# driver.net
KiCad netlist of a schematic drawn in EAGLE
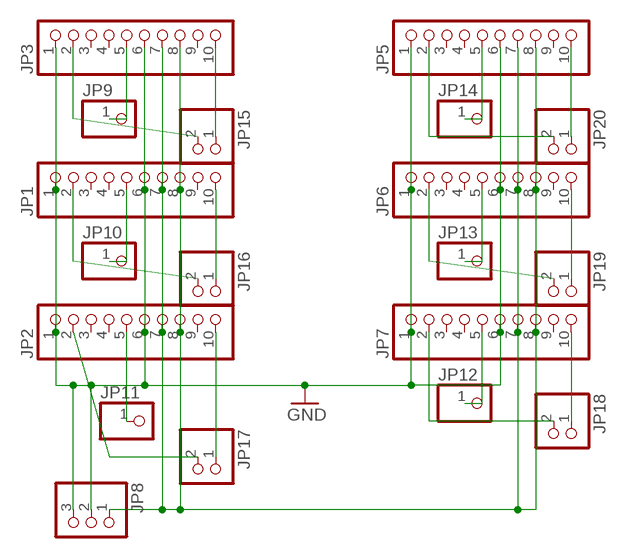
[diagram p0: schematic, sheet 1]

(export (version "E")
  (design (tool "Eeschema 10.0.6"))
  (components
    (comp (ref "JP1")
      (value "PINHD-1X10")
      (footprint "eagle-import:1X10")
      (libsource (lib "eagle-import") (part "PINHD-1X10"))
    )
    (comp (ref "JP2")
      (value "PINHD-1X10")
      (footprint "eagle-import:1X10")
      (libsource (lib "eagle-import") (part "PINHD-1X10"))
    )
    (comp (ref "JP3")
      (value "PINHD-1X10")
      (footprint "eagle-import:1X10")
      (libsource (lib "eagle-import") (part "PINHD-1X10"))
    )
    (comp (ref "JP5")
      (value "PINHD-1X10")
      (footprint "eagle-import:1X10")
      (libsource (lib "eagle-import") (part "PINHD-1X10"))
    )
    (comp (ref "JP6")
      (value "PINHD-1X10")
      (footprint "eagle-import:1X10")
      (libsource (lib "eagle-import") (part "PINHD-1X10"))
    )
    (comp (ref "JP7")
      (value "PINHD-1X10")
      (footprint "eagle-import:1X10")
      (libsource (lib "eagle-import") (part "PINHD-1X10"))
    )
    (comp (ref "JP8")
      (value "PINHD-1X3")
      (footprint "eagle-import:1X03")
      (libsource (lib "eagle-import") (part "PINHD-1X3"))
    )
    (comp (ref "JP9")
      (value "PINHD-1X1")
      (footprint "eagle-import:1X01")
      (libsource (lib "eagle-import") (part "PINHD-1X1"))
    )
    (comp (ref "JP10")
      (value "PINHD-1X1")
      (footprint "eagle-import:1X01")
      (libsource (lib "eagle-import") (part "PINHD-1X1"))
    )
    (comp (ref "JP11")
      (value "PINHD-1X1")
      (footprint "eagle-import:1X01")
      (libsource (lib "eagle-import") (part "PINHD-1X1"))
    )
    (comp (ref "JP12")
      (value "PINHD-1X1")
      (footprint "eagle-import:1X01")
      (libsource (lib "eagle-import") (part "PINHD-1X1"))
    )
    (comp (ref "JP13")
      (value "PINHD-1X1")
      (footprint "eagle-import:1X01")
      (libsource (lib "eagle-import") (part "PINHD-1X1"))
    )
    (comp (ref "JP14")
      (value "PINHD-1X1")
      (footprint "eagle-import:1X01")
      (libsource (lib "eagle-import") (part "PINHD-1X1"))
    )
    (comp (ref "JP15")
      (value "PINHD-1X2")
      (footprint "eagle-import:1X02")
      (libsource (lib "eagle-import") (part "PINHD-1X2"))
    )
    (comp (ref "JP16")
      (value "PINHD-1X2")
      (footprint "eagle-import:1X02")
      (libsource (lib "eagle-import") (part "PINHD-1X2"))
    )
    (comp (ref "JP17")
      (value "PINHD-1X2")
      (footprint "eagle-import:1X02")
      (libsource (lib "eagle-import") (part "PINHD-1X2"))
    )
    (comp (ref "JP18")
      (value "PINHD-1X2")
      (footprint "eagle-import:1X02")
      (libsource (lib "eagle-import") (part "PINHD-1X2"))
    )
    (comp (ref "JP19")
      (value "PINHD-1X2")
      (footprint "eagle-import:1X02")
      (libsource (lib "eagle-import") (part "PINHD-1X2"))
    )
    (comp (ref "JP20")
      (value "PINHD-1X2")
      (footprint "eagle-import:1X02")
      (libsource (lib "eagle-import") (part "PINHD-1X2"))
    )
  )
  (nets
    (net (code "1") (name "GND") (class "Default")
      (node (ref "JP1") (pin "1") (pinfunction "1_1") (pintype "passive"))
      (node (ref "JP1") (pin "6") (pinfunction "6_6") (pintype "passive"))
      (node (ref "JP2") (pin "1") (pinfunction "1_1") (pintype "passive"))
      (node (ref "JP2") (pin "6") (pinfunction "6_6") (pintype "passive"))
      (node (ref "JP3") (pin "1") (pinfunction "1_1") (pintype "passive"))
      (node (ref "JP3") (pin "6") (pinfunction "6_6") (pintype "passive"))
      (node (ref "JP5") (pin "1") (pinfunction "1_1") (pintype "passive"))
      (node (ref "JP5") (pin "6") (pinfunction "6_6") (pintype "passive"))
      (node (ref "JP6") (pin "1") (pinfunction "1_1") (pintype "passive"))
      (node (ref "JP6") (pin "6") (pinfunction "6_6") (pintype "passive"))
      (node (ref "JP7") (pin "1") (pinfunction "1_1") (pintype "passive"))
      (node (ref "JP7") (pin "6") (pinfunction "6_6") (pintype "passive"))
      (node (ref "JP8") (pin "2") (pinfunction "2_2") (pintype "passive"))
      (node (ref "JP8") (pin "3") (pinfunction "3_3") (pintype "passive"))
    )
    (net (code "2") (name "Net-(JP1-Pad2)") (class "Default")
      (node (ref "JP1") (pin "2") (pinfunction "2_2") (pintype "passive"))
      (node (ref "JP16") (pin "2") (pinfunction "2_2") (pintype "passive"))
    )
    (net (code "3") (name "Net-(JP1-Pad5)") (class "Default")
      (node (ref "JP1") (pin "5") (pinfunction "5_5") (pintype "passive"))
      (node (ref "JP10") (pin "1") (pinfunction "1_1") (pintype "passive"))
    )
    (net (code "4") (name "Net-(JP1-Pad7)") (class "Default")
      (node (ref "JP1") (pin "7") (pinfunction "7_7") (pintype "passive"))
      (node (ref "JP1") (pin "8") (pinfunction "8_8") (pintype "passive"))
      (node (ref "JP2") (pin "7") (pinfunction "7_7") (pintype "passive"))
      (node (ref "JP2") (pin "8") (pinfunction "8_8") (pintype "passive"))
      (node (ref "JP3") (pin "7") (pinfunction "7_7") (pintype "passive"))
      (node (ref "JP3") (pin "8") (pinfunction "8_8") (pintype "passive"))
      (node (ref "JP5") (pin "7") (pinfunction "7_7") (pintype "passive"))
      (node (ref "JP5") (pin "8") (pinfunction "8_8") (pintype "passive"))
      (node (ref "JP6") (pin "7") (pinfunction "7_7") (pintype "passive"))
      (node (ref "JP6") (pin "8") (pinfunction "8_8") (pintype "passive"))
      (node (ref "JP7") (pin "7") (pinfunction "7_7") (pintype "passive"))
      (node (ref "JP7") (pin "8") (pinfunction "8_8") (pintype "passive"))
      (node (ref "JP8") (pin "1") (pinfunction "1_1") (pintype "passive"))
    )
    (net (code "5") (name "Net-(JP1-Pad10)") (class "Default")
      (node (ref "JP1") (pin "10") (pinfunction "10_10") (pintype "passive"))
      (node (ref "JP16") (pin "1") (pinfunction "1_1") (pintype "passive"))
    )
    (net (code "6") (name "Net-(JP3-Pad5)") (class "Default")
      (node (ref "JP3") (pin "5") (pinfunction "5_5") (pintype "passive"))
      (node (ref "JP9") (pin "1") (pinfunction "1_1") (pintype "passive"))
    )
    (net (code "7") (name "Net-(JP11-Pad1)") (class "Default")
      (node (ref "JP11") (pin "1") (pinfunction "1_1") (pintype "passive"))
      (node (ref "JP2") (pin "5") (pinfunction "5_5") (pintype "passive"))
    )
    (net (code "8") (name "Net-(JP12-Pad1)") (class "Default")
      (node (ref "JP12") (pin "1") (pinfunction "1_1") (pintype "passive"))
      (node (ref "JP7") (pin "5") (pinfunction "5_5") (pintype "passive"))
    )
    (net (code "9") (name "Net-(JP13-Pad1)") (class "Default")
      (node (ref "JP13") (pin "1") (pinfunction "1_1") (pintype "passive"))
      (node (ref "JP6") (pin "5") (pinfunction "5_5") (pintype "passive"))
    )
    (net (code "10") (name "Net-(JP14-Pad1)") (class "Default")
      (node (ref "JP14") (pin "1") (pinfunction "1_1") (pintype "passive"))
      (node (ref "JP5") (pin "5") (pinfunction "5_5") (pintype "passive"))
    )
    (net (code "11") (name "Net-(JP15-Pad1)") (class "Default")
      (node (ref "JP15") (pin "1") (pinfunction "1_1") (pintype "passive"))
      (node (ref "JP3") (pin "10") (pinfunction "10_10") (pintype "passive"))
    )
    (net (code "12") (name "Net-(JP15-Pad2)") (class "Default")
      (node (ref "JP15") (pin "2") (pinfunction "2_2") (pintype "passive"))
      (node (ref "JP3") (pin "2") (pinfunction "2_2") (pintype "passive"))
    )
    (net (code "13") (name "Net-(JP17-Pad1)") (class "Default")
      (node (ref "JP17") (pin "1") (pinfunction "1_1") (pintype "passive"))
      (node (ref "JP2") (pin "10") (pinfunction "10_10") (pintype "passive"))
    )
    (net (code "14") (name "Net-(JP17-Pad2)") (class "Default")
      (node (ref "JP17") (pin "2") (pinfunction "2_2") (pintype "passive"))
      (node (ref "JP2") (pin "2") (pinfunction "2_2") (pintype "passive"))
    )
    (net (code "15") (name "Net-(JP18-Pad1)") (class "Default")
      (node (ref "JP18") (pin "1") (pinfunction "1_1") (pintype "passive"))
      (node (ref "JP7") (pin "10") (pinfunction "10_10") (pintype "passive"))
    )
    (net (code "16") (name "Net-(JP18-Pad2)") (class "Default")
      (node (ref "JP18") (pin "2") (pinfunction "2_2") (pintype "passive"))
      (node (ref "JP7") (pin "2") (pinfunction "2_2") (pintype "passive"))
    )
    (net (code "17") (name "Net-(JP19-Pad1)") (class "Default")
      (node (ref "JP19") (pin "1") (pinfunction "1_1") (pintype "passive"))
      (node (ref "JP6") (pin "10") (pinfunction "10_10") (pintype "passive"))
    )
    (net (code "18") (name "Net-(JP19-Pad2)") (class "Default")
      (node (ref "JP19") (pin "2") (pinfunction "2_2") (pintype "passive"))
      (node (ref "JP6") (pin "2") (pinfunction "2_2") (pintype "passive"))
    )
    (net (code "19") (name "Net-(JP20-Pad1)") (class "Default")
      (node (ref "JP20") (pin "1") (pinfunction "1_1") (pintype "passive"))
      (node (ref "JP5") (pin "10") (pinfunction "10_10") (pintype "passive"))
    )
    (net (code "20") (name "Net-(JP20-Pad2)") (class "Default")
      (node (ref "JP20") (pin "2") (pinfunction "2_2") (pintype "passive"))
      (node (ref "JP5") (pin "2") (pinfunction "2_2") (pintype "passive"))
    )
    (net (code "21") (name "unconnected-(JP1-Pad3)") (class "Default")
      (node (ref "JP1") (pin "3") (pinfunction "3_3") (pintype "passive"))
    )
    (net (code "22") (name "unconnected-(JP1-Pad4)") (class "Default")
      (node (ref "JP1") (pin "4") (pinfunction "4_4") (pintype "passive"))
    )
    (net (code "23") (name "unconnected-(JP1-Pad9)") (class "Default")
      (node (ref "JP1") (pin "9") (pinfunction "9_9") (pintype "passive"))
    )
    (net (code "24") (name "unconnected-(JP2-Pad3)") (class "Default")
      (node (ref "JP2") (pin "3") (pinfunction "3_3") (pintype "passive"))
    )
    (net (code "25") (name "unconnected-(JP2-Pad4)") (class "Default")
      (node (ref "JP2") (pin "4") (pinfunction "4_4") (pintype "passive"))
    )
    (net (code "26") (name "unconnected-(JP2-Pad9)") (class "Default")
      (node (ref "JP2") (pin "9") (pinfunction "9_9") (pintype "passive"))
    )
    (net (code "27") (name "unconnected-(JP3-Pad3)") (class "Default")
      (node (ref "JP3") (pin "3") (pinfunction "3_3") (pintype "passive"))
    )
    (net (code "28") (name "unconnected-(JP3-Pad4)") (class "Default")
      (node (ref "JP3") (pin "4") (pinfunction "4_4") (pintype "passive"))
    )
    (net (code "29") (name "unconnected-(JP3-Pad9)") (class "Default")
      (node (ref "JP3") (pin "9") (pinfunction "9_9") (pintype "passive"))
    )
    (net (code "30") (name "unconnected-(JP5-Pad3)") (class "Default")
      (node (ref "JP5") (pin "3") (pinfunction "3_3") (pintype "passive"))
    )
    (net (code "31") (name "unconnected-(JP5-Pad4)") (class "Default")
      (node (ref "JP5") (pin "4") (pinfunction "4_4") (pintype "passive"))
    )
    (net (code "32") (name "unconnected-(JP5-Pad9)") (class "Default")
      (node (ref "JP5") (pin "9") (pinfunction "9_9") (pintype "passive"))
    )
    (net (code "33") (name "unconnected-(JP6-Pad3)") (class "Default")
      (node (ref "JP6") (pin "3") (pinfunction "3_3") (pintype "passive"))
    )
    (net (code "34") (name "unconnected-(JP6-Pad4)") (class "Default")
      (node (ref "JP6") (pin "4") (pinfunction "4_4") (pintype "passive"))
    )
    (net (code "35") (name "unconnected-(JP6-Pad9)") (class "Default")
      (node (ref "JP6") (pin "9") (pinfunction "9_9") (pintype "passive"))
    )
    (net (code "36") (name "unconnected-(JP7-Pad3)") (class "Default")
      (node (ref "JP7") (pin "3") (pinfunction "3_3") (pintype "passive"))
    )
    (net (code "37") (name "unconnected-(JP7-Pad4)") (class "Default")
      (node (ref "JP7") (pin "4") (pinfunction "4_4") (pintype "passive"))
    )
    (net (code "38") (name "unconnected-(JP7-Pad9)") (class "Default")
      (node (ref "JP7") (pin "9") (pinfunction "9_9") (pintype "passive"))
    )
  )
)
